# ADC-SYNC_INPUT.net
KiCad netlist of a schematic drawn in Altium Designer
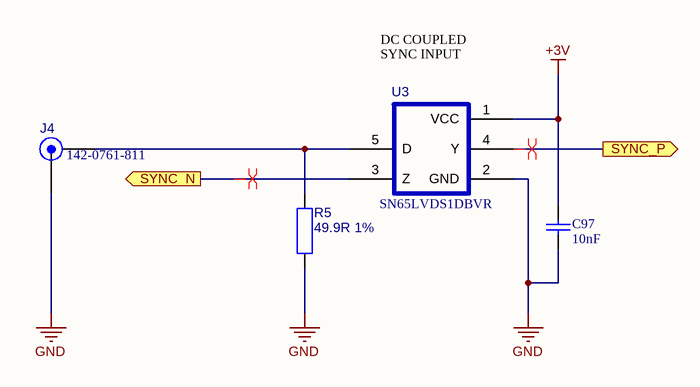
[diagram p0: ADC-SYNC INPUT.SchDoc]

(export (version "E")
  (design (tool "Eeschema 10.0.6"))
  (components
    (comp (ref "C97")
      (value "10nF")
      (footprint "CAPC1005X55N")
      (description "Capacitor 0402 SMD")
      (fields (field (name "CREATED_BY") "EDA-ASA") (field (name "CHECKED_BY") "*"))
      (libsource (lib "EDA-Passive") (part "cap0402"))
    )
    (comp (ref "J4")
      (value "142-0761-811")
      (footprint "EDGE_LAUNCH_TH_SMA")
      (description "High Frequency SMA End Lauch Connector")
      (fields
        (field (name "MANUFACTURER") "JOHNSON")
        (field (name "MANUFACTURER_PN") "142-0761-811")
        (field (name "CREATED_BY") "CT")
        (field (name "CHECKED_BY") "*")
      )
      (libsource (lib "Charles-TEMP") (part "142-0761-811"))
    )
    (comp (ref "R5")
      (value "49.9R 1%")
      (footprint "0603")
      (description "RESISTOR SMD 0603")
      (fields (field (name "CREATED_BY") "*") (field (name "CHECKED_BY") "NN"))
      (libsource (lib "EDA_Passive") (part "RES-0805"))
    )
    (comp (ref "U3")
      (value "SN65LVDS1DBVR")
      (footprint "SOT95P280X145-5N")
      (description "High Speed Differential Line Driver/Receiver")
      (fields
        (field (name "MANUFACTURER") "TI")
        (field (name "CREATED_BY") "IN")
        (field (name "CHECKED_BY") "*")
      )
      (libsource (lib "Ishvah-TEMP") (part "SN65LVDS1DBVR"))
    )
  )
  (nets
    (net (code "1") (name "+3V") (class "Default")
      (node (ref "C97") (pin "2") (pinfunction "2_2") (pintype "passive"))
      (node (ref "U3") (pin "1") (pinfunction "VCC_1") (pintype "passive"))
    )
    (net (code "2") (name "/SYNC_N") (class "Default")
      (node (ref "U3") (pin "3") (pinfunction "Z_3") (pintype "passive"))
    )
    (net (code "3") (name "/SYNC_P") (class "Default")
      (node (ref "U3") (pin "4") (pinfunction "Y_4") (pintype "passive"))
    )
    (net (code "4") (name "GND") (class "Default")
      (node (ref "C97") (pin "1") (pinfunction "1_1") (pintype "passive"))
      (node (ref "J4") (pin "2") (pinfunction "2_2") (pintype "passive"))
      (node (ref "R5") (pin "2") (pinfunction "2_2") (pintype "passive"))
      (node (ref "U3") (pin "2") (pinfunction "GND_2") (pintype "passive"))
    )
    (net (code "5") (name "Net-(U3-D)") (class "Default")
      (node (ref "J4") (pin "1") (pinfunction "1_1") (pintype "passive"))
      (node (ref "R5") (pin "1") (pinfunction "1_1") (pintype "passive"))
      (node (ref "U3") (pin "5") (pinfunction "D_5") (pintype "passive"))
    )
  )
)
